# Power.net
KiCad netlist of a schematic drawn in Altium Designer
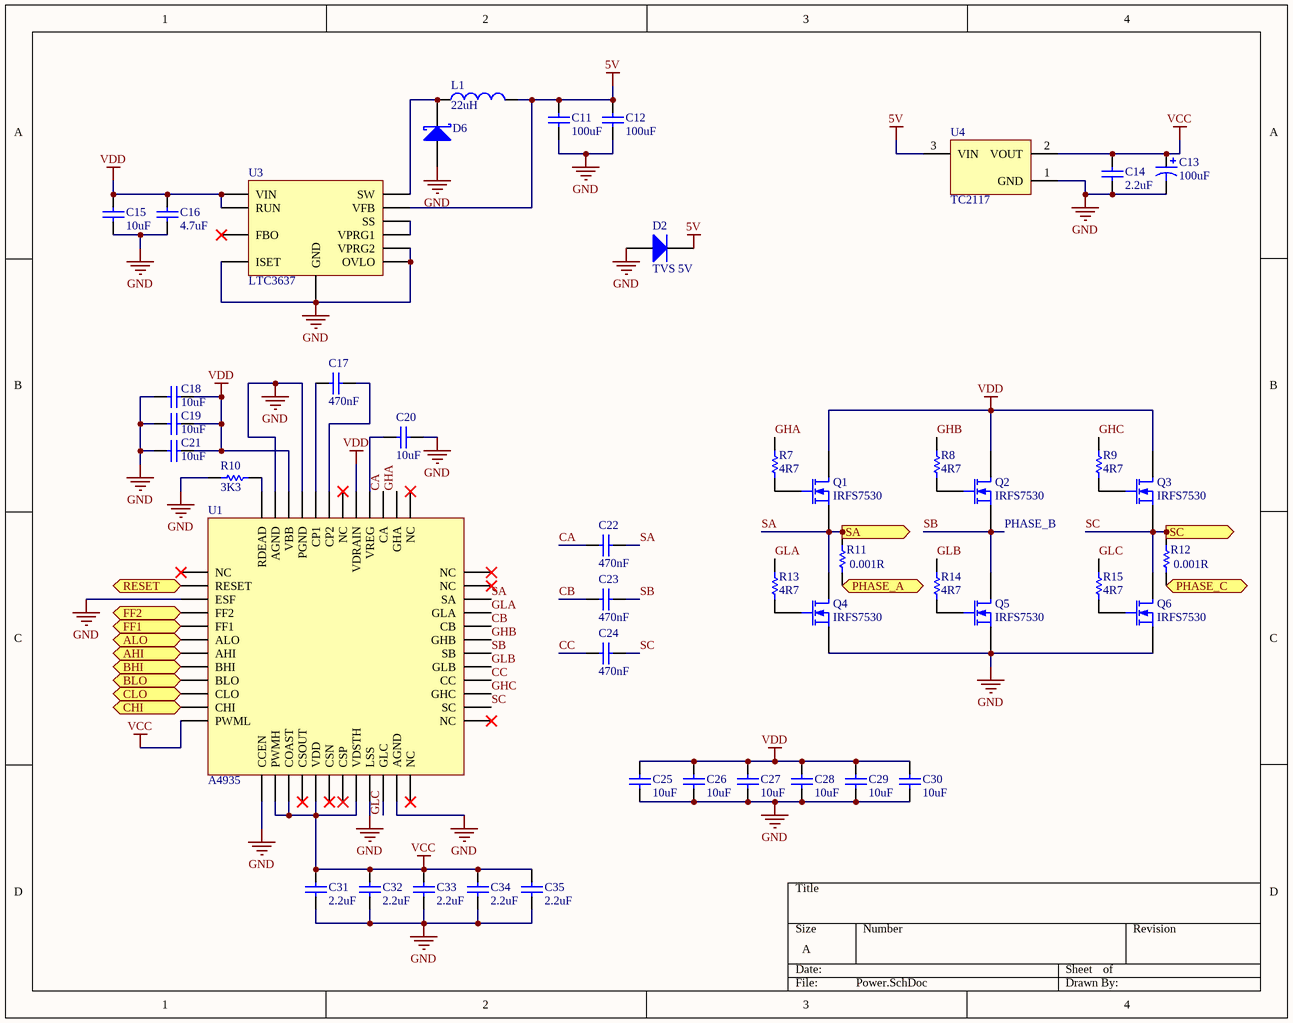
[diagram p0: Power.SchDoc]

(export (version "E")
  (design (tool "Eeschema 10.0.6"))
  (components
    (comp (ref "C11")
      (value "100uF")
      (footprint "CAPC1210(3225)280_N")
      (description "CAP 100uF 10V Â±10% 1210 (3225 Metric) Thickness 2.8mm SMD")
      (fields (field (name "TOLERANCE") "Â±10%"))
      (libsource (lib "Altium Content Vault") (part "CMP-1038-02301-1"))
    )
    (comp (ref "C12")
      (value "100uF")
      (footprint "CAPC1210(3225)280_N")
      (description "CAP 100uF 10V Â±10% 1210 (3225 Metric) Thickness 2.8mm SMD")
      (fields (field (name "TOLERANCE") "Â±10%"))
      (libsource (lib "Altium Content Vault") (part "CMP-1038-02301-1"))
    )
    (comp (ref "C13")
      (value "100uF")
      (footprint "AVX-CAPC7343_V")
      (libsource (lib "Components") (part "AVX-CAP-P-2"))
    )
    (comp (ref "C14")
      (value "2.2uF")
      (footprint "CAPC0603(1608)55_N")
      (description "CAP 2.2uF 16V Â±10% 0603 (1608 Metric) Thickness 0.55mm SMD")
      (fields (field (name "TOLERANCE") "Â±10%"))
      (libsource (lib "Altium Content Vault") (part "CMP-1035-02762-1"))
    )
    (comp (ref "C15")
      (value "10uF")
      (footprint "CAPC1206(3216)190_M")
      (description "CAP 10uF 50V Â±10% 1206 (3216 Metric) Thickness 1.9mm SMD")
      (fields (field (name "TOLERANCE") "Â±10%"))
      (libsource (lib "Altium Content Vault") (part "CAP"))
    )
    (comp (ref "C16")
      (value "4.7uF")
      (footprint "CAPC0805(2012)145_N")
      (description "CAP 4.7uF 50V Â±10% 0805 (2012 Metric) Thickness 1.45mm SMD")
      (fields (field (name "TOLERANCE") "Â±10%"))
      (libsource (lib "Altium Content Vault") (part "CAP"))
    )
    (comp (ref "C17")
      (value "470nF")
      (footprint "CAPC0603(1608)100_N")
      (description "CAP 470nF 25V Â±20% 0603 (1608 Metric) Thickness 1mm SMD")
      (fields (field (name "TOLERANCE") "Â±20%"))
      (libsource (lib "Altium Content Vault") (part "CAP"))
    )
    (comp (ref "C18")
      (value "10uF")
      (footprint "CAPC1206(3216)190_M")
      (description "CAP 10uF 50V Â±10% 1206 (3216 Metric) Thickness 1.9mm SMD")
      (fields (field (name "TOLERANCE") "Â±10%"))
      (libsource (lib "Altium Content Vault") (part "CAP"))
    )
    (comp (ref "C19")
      (value "10uF")
      (footprint "CAPC1206(3216)190_M")
      (description "CAP 10uF 50V Â±10% 1206 (3216 Metric) Thickness 1.9mm SMD")
      (fields (field (name "TOLERANCE") "Â±10%"))
      (libsource (lib "Altium Content Vault") (part "CAP"))
    )
    (comp (ref "C20")
      (value "10uF")
      (footprint "CAPC0805(2012)145_N")
      (description "CAP 10uF 25V Â±10% 0805 (2012 Metric) Thickness 1.45mm SMD")
      (fields (field (name "TOLERANCE") "Â±10%"))
      (libsource (lib "Altium Content Vault") (part "CAP"))
    )
    (comp (ref "C21")
      (value "10uF")
      (footprint "CAPC1206(3216)190_M")
      (description "CAP 10uF 50V Â±10% 1206 (3216 Metric) Thickness 1.9mm SMD")
      (fields (field (name "TOLERANCE") "Â±10%"))
      (libsource (lib "Altium Content Vault") (part "CAP"))
    )
    (comp (ref "C22")
      (value "470nF")
      (footprint "CAPC0603(1608)100_L")
      (description "CAP 470nF 25V Â±10% 0603 (1608 Metric) Thickness 1mm SMD")
      (fields (field (name "TOLERANCE") "Â±10%"))
      (libsource (lib "Altium Content Vault") (part "CAP"))
    )
    (comp (ref "C23")
      (value "470nF")
      (footprint "CAPC0603(1608)100_L")
      (description "CAP 470nF 25V Â±10% 0603 (1608 Metric) Thickness 1mm SMD")
      (fields (field (name "TOLERANCE") "Â±10%"))
      (libsource (lib "Altium Content Vault") (part "CAP"))
    )
    (comp (ref "C24")
      (value "470nF")
      (footprint "CAPC0603(1608)100_L")
      (description "CAP 470nF 25V Â±10% 0603 (1608 Metric) Thickness 1mm SMD")
      (fields (field (name "TOLERANCE") "Â±10%"))
      (libsource (lib "Altium Content Vault") (part "CAP"))
    )
    (comp (ref "C25")
      (value "10uF")
      (footprint "CAPC1206(3216)190_M")
      (description "CAP 10uF 50V Â±10% 1206 (3216 Metric) Thickness 1.9mm SMD")
      (fields (field (name "TOLERANCE") "Â±10%"))
      (libsource (lib "Altium Content Vault") (part "CMP-1037-04982-1"))
    )
    (comp (ref "C26")
      (value "10uF")
      (footprint "CAPC1206(3216)190_M")
      (description "CAP 10uF 50V Â±10% 1206 (3216 Metric) Thickness 1.9mm SMD")
      (fields (field (name "TOLERANCE") "Â±10%"))
      (libsource (lib "Altium Content Vault") (part "CAP"))
    )
    (comp (ref "C27")
      (value "10uF")
      (footprint "CAPC1206(3216)190_M")
      (description "CAP 10uF 50V Â±10% 1206 (3216 Metric) Thickness 1.9mm SMD")
      (fields (field (name "TOLERANCE") "Â±10%"))
      (libsource (lib "Altium Content Vault") (part "CAP"))
    )
    (comp (ref "C28")
      (value "10uF")
      (footprint "CAPC1206(3216)190_M")
      (description "CAP 10uF 50V Â±10% 1206 (3216 Metric) Thickness 1.9mm SMD")
      (fields (field (name "TOLERANCE") "Â±10%"))
      (libsource (lib "Altium Content Vault") (part "CMP-1037-04982-1"))
    )
    (comp (ref "C29")
      (value "10uF")
      (footprint "CAPC1206(3216)190_M")
      (description "CAP 10uF 50V Â±10% 1206 (3216 Metric) Thickness 1.9mm SMD")
      (fields (field (name "TOLERANCE") "Â±10%"))
      (libsource (lib "Altium Content Vault") (part "CAP"))
    )
    (comp (ref "C30")
      (value "10uF")
      (footprint "CAPC1206(3216)190_M")
      (description "CAP 10uF 50V Â±10% 1206 (3216 Metric) Thickness 1.9mm SMD")
      (fields (field (name "TOLERANCE") "Â±10%"))
      (libsource (lib "Altium Content Vault") (part "CAP"))
    )
    (comp (ref "C31")
      (value "2.2uF")
      (footprint "CAPC0603(1608)55_N")
      (description "CAP 2.2uF 16V Â±10% 0603 (1608 Metric) Thickness 0.55mm SMD")
      (fields (field (name "TOLERANCE") "Â±10%"))
      (libsource (lib "Altium Content Vault") (part "CMP-1035-02762-1"))
    )
    (comp (ref "C32")
      (value "2.2uF")
      (footprint "CAPC0603(1608)55_N")
      (description "CAP 2.2uF 16V Â±10% 0603 (1608 Metric) Thickness 0.55mm SMD")
      (fields (field (name "TOLERANCE") "Â±10%"))
      (libsource (lib "Altium Content Vault") (part "CMP-1035-02762-1"))
    )
    (comp (ref "C33")
      (value "2.2uF")
      (footprint "CAPC0603(1608)55_N")
      (description "CAP 2.2uF 16V Â±10% 0603 (1608 Metric) Thickness 0.55mm SMD")
      (fields (field (name "TOLERANCE") "Â±10%"))
      (libsource (lib "Altium Content Vault") (part "CMP-1035-02762-1"))
    )
    (comp (ref "C34")
      (value "2.2uF")
      (footprint "CAPC0603(1608)55_N")
      (description "CAP 2.2uF 16V Â±10% 0603 (1608 Metric) Thickness 0.55mm SMD")
      (fields (field (name "TOLERANCE") "Â±10%"))
      (libsource (lib "Altium Content Vault") (part "CMP-1035-02762-1"))
    )
    (comp (ref "C35")
      (value "2.2uF")
      (footprint "CAPC0603(1608)55_N")
      (description "CAP 2.2uF 16V Â±10% 0603 (1608 Metric) Thickness 0.55mm SMD")
      (fields (field (name "TOLERANCE") "Â±10%"))
      (libsource (lib "Altium Content Vault") (part "CMP-1035-02762-1"))
    )
    (comp (ref "D2")
      (value "TVS 5V")
      (footprint "VISH-DO-214AC-2_N")
      (fields
        (field (name "PARTNUMBER") "SMAJ5.0A-E3/61")
        (field (name "MANUFACTURER") "Vishay Semiconductor")
      )
      (libsource (lib "Altium Content Vault") (part "CMP-0548-00235-1"))
    )
    (comp (ref "D6")
      (value "~")
      (footprint "SMB")
      (description "Schottky Diode")
      (fields (field (name "PUBLISHER") "Altium Limited"))
      (libsource (lib "Miscellaneous Devices") (part "D Schottky"))
    )
    (comp (ref "L1")
      (value "22uH")
      (footprint "SDR0805-180ML")
      (description "Inductor")
      (fields (field (name "Comment") "SDR0805-180ML") (field (name "PUBLISHER") "Altium Limited"))
      (libsource (lib "Components") (part "SDR0805-180ML"))
    )
    (comp (ref "Q1")
      (value "IRFS7530")
      (footprint "DPAK127P1525X483-7N")
      (description "N-Channel MOSFET")
      (fields (field (name "PUBLISHER") "Altium Limited"))
      (libsource (lib "Components") (part "IRFS7530"))
    )
    (comp (ref "Q2")
      (value "IRFS7530")
      (footprint "DPAK127P1525X483-7N")
      (description "N-Channel MOSFET")
      (fields (field (name "PUBLISHER") "Altium Limited"))
      (libsource (lib "Components") (part "IRFS7530"))
    )
    (comp (ref "Q3")
      (value "IRFS7530")
      (footprint "DPAK127P1525X483-7N")
      (description "N-Channel MOSFET")
      (fields (field (name "PUBLISHER") "Altium Limited"))
      (libsource (lib "Components") (part "IRFS7530"))
    )
    (comp (ref "Q4")
      (value "IRFS7530")
      (footprint "DPAK127P1525X483-7N")
      (description "N-Channel MOSFET")
      (fields (field (name "PUBLISHER") "Altium Limited"))
      (libsource (lib "Components") (part "IRFS7530"))
    )
    (comp (ref "Q5")
      (value "IRFS7530")
      (footprint "DPAK127P1525X483-7N")
      (description "N-Channel MOSFET")
      (fields (field (name "PUBLISHER") "Altium Limited"))
      (libsource (lib "Components") (part "IRFS7530"))
    )
    (comp (ref "Q6")
      (value "IRFS7530")
      (footprint "DPAK127P1525X483-7N")
      (description "N-Channel MOSFET")
      (fields (field (name "PUBLISHER") "Altium Limited"))
      (libsource (lib "Components") (part "IRFS7530"))
    )
    (comp (ref "R7")
      (value "4R7")
      (footprint "RESC0603(1608)_N")
      (description "4R7 0.1W 5% 0603 (1608 Metric)  SMD")
      (fields (field (name "POWER") "0.1 W") (field (name "TOLERANCE") "5 %"))
      (libsource (lib "Altium Content Vault") (part "CMP-1012-00018-1"))
    )
    (comp (ref "R8")
      (value "4R7")
      (footprint "RESC0603(1608)_N")
      (description "4R7 0.1W 5% 0603 (1608 Metric)  SMD")
      (fields (field (name "POWER") "0.1 W") (field (name "TOLERANCE") "5 %"))
      (libsource (lib "Altium Content Vault") (part "CMP-1012-00018-1"))
    )
    (comp (ref "R9")
      (value "4R7")
      (footprint "RESC0603(1608)_N")
      (description "4R7 0.1W 5% 0603 (1608 Metric)  SMD")
      (fields (field (name "POWER") "0.1 W") (field (name "TOLERANCE") "5 %"))
      (libsource (lib "Altium Content Vault") (part "CMP-1012-00018-1"))
    )
    (comp (ref "R10")
      (value "3K3")
      (footprint "RESC0603(1608)_N")
      (description "3K3 0.1W 5% 0603 (1608 Metric)  SMD")
      (fields (field (name "TOLERANCE") "5 %") (field (name "POWER") "0.1 W"))
      (libsource (lib "Altium Content Vault") (part "CMP-1012-00086-1"))
    )
    (comp (ref "R11")
      (value "0.001R")
      (footprint "Shunt")
      (fields (field (name "PUBLISHER") "Altium Limited"))
      (libsource (lib "Components") (part "Shunt"))
    )
    (comp (ref "R12")
      (value "0.001R")
      (footprint "Shunt")
      (description "Resistor")
      (fields (field (name "PUBLISHER") "Altium Limited"))
      (libsource (lib "Components") (part "Shunt"))
    )
    (comp (ref "R13")
      (value "4R7")
      (footprint "RESC0603(1608)_N")
      (description "4R7 0.1W 5% 0603 (1608 Metric)  SMD")
      (fields (field (name "POWER") "0.1 W") (field (name "TOLERANCE") "5 %"))
      (libsource (lib "Altium Content Vault") (part "CMP-1012-00018-1"))
    )
    (comp (ref "R14")
      (value "4R7")
      (footprint "RESC0603(1608)_N")
      (description "4R7 0.1W 5% 0603 (1608 Metric)  SMD")
      (fields (field (name "POWER") "0.1 W") (field (name "TOLERANCE") "5 %"))
      (libsource (lib "Altium Content Vault") (part "CMP-1012-00018-1"))
    )
    (comp (ref "R15")
      (value "4R7")
      (footprint "RESC0603(1608)_N")
      (description "4R7 0.1W 5% 0603 (1608 Metric)  SMD")
      (fields (field (name "POWER") "0.1 W") (field (name "TOLERANCE") "5 %"))
      (libsource (lib "Altium Content Vault") (part "CMP-1012-00018-1"))
    )
    (comp (ref "U1") (value "A4935") (footprint "LQFP-48") (libsource (lib "Components") (part "A4935")))
    (comp (ref "U3")
      (value "LTC3637")
      (footprint "SON50P300X85_HS-17N")
      (libsource (lib "Components") (part "LTC3637"))
    )
    (comp (ref "U4")
      (value "TC2117")
      (footprint "SOT-223-DB3_M")
      (libsource (lib "Components") (part "PM-LINEREG-TC2117-IL4"))
    )
  )
  (nets
    (net (code "1") (name "/AHI") (class "Default")
      (node (ref "U1") (pin "7") (pinfunction "AHI_7") (pintype "passive"))
    )
    (net (code "2") (name "/ALO") (class "Default")
      (node (ref "U1") (pin "6") (pinfunction "ALO_6") (pintype "passive"))
    )
    (net (code "3") (name "/BHI") (class "Default")
      (node (ref "U1") (pin "8") (pinfunction "BHI_8") (pintype "passive"))
    )
    (net (code "4") (name "/BLO") (class "Default")
      (node (ref "U1") (pin "9") (pinfunction "BLO_9") (pintype "passive"))
    )
    (net (code "5") (name "/CA") (class "Default")
      (node (ref "C22") (pin "1") (pinfunction "1_1") (pintype "passive"))
      (node (ref "U1") (pin "39") (pinfunction "CA_39") (pintype "passive"))
    )
    (net (code "6") (name "/CB") (class "Default")
      (node (ref "C23") (pin "1") (pinfunction "1_1") (pintype "passive"))
      (node (ref "U1") (pin "32") (pinfunction "CB_32") (pintype "passive"))
    )
    (net (code "7") (name "/CC") (class "Default")
      (node (ref "C24") (pin "1") (pinfunction "1_1") (pintype "passive"))
      (node (ref "U1") (pin "28") (pinfunction "CC_28") (pintype "passive"))
    )
    (net (code "8") (name "/CHI") (class "Default")
      (node (ref "U1") (pin "11") (pinfunction "CHI_11") (pintype "passive"))
    )
    (net (code "9") (name "/CLO") (class "Default")
      (node (ref "U1") (pin "10") (pinfunction "CLO_10") (pintype "passive"))
    )
    (net (code "10") (name "/FF1") (class "Default")
      (node (ref "U1") (pin "5") (pinfunction "FF1_5") (pintype "passive"))
    )
    (net (code "11") (name "/FF2") (class "Default")
      (node (ref "U1") (pin "4") (pinfunction "FF2_4") (pintype "passive"))
    )
    (net (code "12") (name "/GHA") (class "Default")
      (node (ref "R7") (pin "2") (pinfunction "2_2") (pintype "passive"))
      (node (ref "U1") (pin "38") (pinfunction "GHA_38") (pintype "passive"))
    )
    (net (code "13") (name "/GHB") (class "Default")
      (node (ref "R8") (pin "2") (pinfunction "2_2") (pintype "passive"))
      (node (ref "U1") (pin "31") (pinfunction "GHB_31") (pintype "passive"))
    )
    (net (code "14") (name "/GHC") (class "Default")
      (node (ref "R9") (pin "2") (pinfunction "2_2") (pintype "passive"))
      (node (ref "U1") (pin "27") (pinfunction "GHC_27") (pintype "passive"))
    )
    (net (code "15") (name "/GLA") (class "Default")
      (node (ref "R13") (pin "2") (pinfunction "2_2") (pintype "passive"))
      (node (ref "U1") (pin "33") (pinfunction "GLA_33") (pintype "passive"))
    )
    (net (code "16") (name "/GLB") (class "Default")
      (node (ref "R14") (pin "2") (pinfunction "2_2") (pintype "passive"))
      (node (ref "U1") (pin "29") (pinfunction "GLB_29") (pintype "passive"))
    )
    (net (code "17") (name "/GLC") (class "Default")
      (node (ref "R15") (pin "2") (pinfunction "2_2") (pintype "passive"))
      (node (ref "U1") (pin "22") (pinfunction "GLC_22") (pintype "passive"))
    )
    (net (code "18") (name "/PHASE_A") (class "Default")
      (node (ref "R11") (pin "1") (pinfunction "1_1") (pintype "passive"))
    )
    (net (code "19") (name "/PHASE_C") (class "Default")
      (node (ref "R12") (pin "1") (pinfunction "1_1") (pintype "passive"))
    )
    (net (code "20") (name "/RESET") (class "Default")
      (node (ref "U1") (pin "2") (pinfunction "RESET_2") (pintype "passive"))
    )
    (net (code "21") (name "/SA") (class "Default")
      (node (ref "C22") (pin "2") (pinfunction "2_2") (pintype "passive"))
      (node (ref "Q1") (pin "3") (pinfunction "S_3") (pintype "passive"))
      (node (ref "Q4") (pin "1") (pinfunction "D_1") (pintype "passive"))
      (node (ref "R11") (pin "2") (pinfunction "2_2") (pintype "passive"))
      (node (ref "U1") (pin "34") (pinfunction "SA_34") (pintype "passive"))
    )
    (net (code "22") (name "/SB") (class "Default")
      (node (ref "C23") (pin "2") (pinfunction "2_2") (pintype "passive"))
      (node (ref "Q2") (pin "3") (pinfunction "S_3") (pintype "passive"))
      (node (ref "Q5") (pin "1") (pinfunction "D_1") (pintype "passive"))
      (node (ref "U1") (pin "30") (pinfunction "SB_30") (pintype "passive"))
    )
    (net (code "23") (name "/SC") (class "Default")
      (node (ref "C24") (pin "2") (pinfunction "2_2") (pintype "passive"))
      (node (ref "Q3") (pin "3") (pinfunction "S_3") (pintype "passive"))
      (node (ref "Q6") (pin "1") (pinfunction "D_1") (pintype "passive"))
      (node (ref "R12") (pin "2") (pinfunction "2_2") (pintype "passive"))
      (node (ref "U1") (pin "26") (pinfunction "SC_26") (pintype "passive"))
    )
    (net (code "24") (name "5V") (class "Default")
      (node (ref "C11") (pin "2") (pinfunction "2_2") (pintype "passive"))
      (node (ref "C12") (pin "2") (pinfunction "2_2") (pintype "passive"))
      (node (ref "D2") (pin "1") (pinfunction "K_1") (pintype "passive"))
      (node (ref "L1") (pin "2") (pinfunction "2_2") (pintype "passive"))
      (node (ref "U3") (pin "9") (pinfunction "VFB_9") (pintype "passive"))
      (node (ref "U4") (pin "3") (pinfunction "VIN_3") (pintype "power_in"))
    )
    (net (code "25") (name "GND") (class "Default")
      (node (ref "C11") (pin "1") (pinfunction "1_1") (pintype "passive"))
      (node (ref "C12") (pin "1") (pinfunction "1_1") (pintype "passive"))
      (node (ref "C13") (pin "2") (pinfunction "2_2") (pintype "passive"))
      (node (ref "C14") (pin "2") (pinfunction "2_2") (pintype "passive"))
      (node (ref "C15") (pin "1") (pinfunction "1_1") (pintype "passive"))
      (node (ref "C16") (pin "2") (pinfunction "2_2") (pintype "passive"))
      (node (ref "C18") (pin "1") (pinfunction "1_1") (pintype "passive"))
      (node (ref "C19") (pin "1") (pinfunction "1_1") (pintype "passive"))
      (node (ref "C20") (pin "2") (pinfunction "2_2") (pintype "passive"))
      (node (ref "C21") (pin "1") (pinfunction "1_1") (pintype "passive"))
      (node (ref "C25") (pin "1") (pinfunction "1_1") (pintype "passive"))
      (node (ref "C26") (pin "1") (pinfunction "1_1") (pintype "passive"))
      (node (ref "C27") (pin "1") (pinfunction "1_1") (pintype "passive"))
      (node (ref "C28") (pin "1") (pinfunction "1_1") (pintype "passive"))
      (node (ref "C29") (pin "1") (pinfunction "1_1") (pintype "passive"))
      (node (ref "C30") (pin "1") (pinfunction "1_1") (pintype "passive"))
      (node (ref "C31") (pin "1") (pinfunction "1_1") (pintype "passive"))
      (node (ref "C32") (pin "1") (pinfunction "1_1") (pintype "passive"))
      (node (ref "C33") (pin "1") (pinfunction "1_1") (pintype "passive"))
      (node (ref "C34") (pin "1") (pinfunction "1_1") (pintype "passive"))
      (node (ref "C35") (pin "1") (pinfunction "1_1") (pintype "passive"))
      (node (ref "D2") (pin "2") (pinfunction "A_2") (pintype "passive"))
      (node (ref "D6") (pin "1") (pinfunction "A_1") (pintype "passive"))
      (node (ref "Q4") (pin "3") (pinfunction "S_3") (pintype "passive"))
      (node (ref "Q5") (pin "3") (pinfunction "S_3") (pintype "passive"))
      (node (ref "Q6") (pin "3") (pinfunction "S_3") (pintype "passive"))
      (node (ref "R10") (pin "1") (pinfunction "1_1") (pintype "passive"))
      (node (ref "U1") (pin "13") (pinfunction "CCEN_13") (pintype "passive"))
      (node (ref "U1") (pin "21") (pinfunction "LSS_21") (pintype "passive"))
      (node (ref "U1") (pin "23") (pinfunction "AGND_23") (pintype "passive"))
      (node (ref "U1") (pin "3") (pinfunction "ESF_3") (pintype "passive"))
      (node (ref "U1") (pin "45") (pinfunction "PGND_45") (pintype "passive"))
      (node (ref "U1") (pin "47") (pinfunction "AGND_47") (pintype "passive"))
      (node (ref "U3") (pin "11") (pinfunction "ISET_11") (pintype "passive"))
      (node (ref "U3") (pin "12") (pinfunction "OVLO_12") (pintype "passive"))
      (node (ref "U3") (pin "17") (pinfunction "GND_17") (pintype "passive"))
      (node (ref "U3") (pin "6") (pinfunction "VPRG2_6") (pintype "passive"))
      (node (ref "U4") (pin "1") (pinfunction "GND_1") (pintype "power_in"))
    )
    (net (code "26") (name "Net-(D6-K)") (class "Default")
      (node (ref "D6") (pin "2") (pinfunction "K_2") (pintype "passive"))
      (node (ref "L1") (pin "1") (pinfunction "1_1") (pintype "passive"))
      (node (ref "U3") (pin "1") (pinfunction "SW_1") (pintype "passive"))
    )
    (net (code "27") (name "Net-(Q1-G)") (class "Default")
      (node (ref "Q1") (pin "2") (pinfunction "G_2") (pintype "passive"))
      (node (ref "R7") (pin "1") (pinfunction "1_1") (pintype "passive"))
    )
    (net (code "28") (name "Net-(Q2-G)") (class "Default")
      (node (ref "Q2") (pin "2") (pinfunction "G_2") (pintype "passive"))
      (node (ref "R8") (pin "1") (pinfunction "1_1") (pintype "passive"))
    )
    (net (code "29") (name "Net-(Q3-G)") (class "Default")
      (node (ref "Q3") (pin "2") (pinfunction "G_2") (pintype "passive"))
      (node (ref "R9") (pin "1") (pinfunction "1_1") (pintype "passive"))
    )
    (net (code "30") (name "Net-(Q4-G)") (class "Default")
      (node (ref "Q4") (pin "2") (pinfunction "G_2") (pintype "passive"))
      (node (ref "R13") (pin "1") (pinfunction "1_1") (pintype "passive"))
    )
    (net (code "31") (name "Net-(Q5-G)") (class "Default")
      (node (ref "Q5") (pin "2") (pinfunction "G_2") (pintype "passive"))
      (node (ref "R14") (pin "1") (pinfunction "1_1") (pintype "passive"))
    )
    (net (code "32") (name "Net-(Q6-G)") (class "Default")
      (node (ref "Q6") (pin "2") (pinfunction "G_2") (pintype "passive"))
      (node (ref "R15") (pin "1") (pinfunction "1_1") (pintype "passive"))
    )
    (net (code "33") (name "Net-(U1-CP1)") (class "Default")
      (node (ref "C17") (pin "1") (pinfunction "1_1") (pintype "passive"))
      (node (ref "U1") (pin "44") (pinfunction "CP1_44") (pintype "passive"))
    )
    (net (code "34") (name "Net-(U1-CP2)") (class "Default")
      (node (ref "C17") (pin "2") (pinfunction "2_2") (pintype "passive"))
      (node (ref "U1") (pin "43") (pinfunction "CP2_43") (pintype "passive"))
    )
    (net (code "35") (name "Net-(U1-RDEAD)") (class "Default")
      (node (ref "R10") (pin "2") (pinfunction "2_2") (pintype "passive"))
      (node (ref "U1") (pin "48") (pinfunction "RDEAD_48") (pintype "passive"))
    )
    (net (code "36") (name "Net-(U1-VREG)") (class "Default")
      (node (ref "C20") (pin "1") (pinfunction "1_1") (pintype "passive"))
      (node (ref "U1") (pin "40") (pinfunction "VREG_40") (pintype "passive"))
    )
    (net (code "37") (name "Net-(U3-SS)") (class "Default")
      (node (ref "U3") (pin "10") (pinfunction "SS_10") (pintype "passive"))
      (node (ref "U3") (pin "7") (pinfunction "VPRG1_7") (pintype "passive"))
    )
    (net (code "38") (name "VCC") (class "Default")
      (node (ref "C13") (pin "1") (pinfunction "1_1") (pintype "passive"))
      (node (ref "C14") (pin "1") (pinfunction "1_1") (pintype "passive"))
      (node (ref "C31") (pin "2") (pinfunction "2_2") (pintype "passive"))
      (node (ref "C32") (pin "2") (pinfunction "2_2") (pintype "passive"))
      (node (ref "C33") (pin "2") (pinfunction "2_2") (pintype "passive"))
      (node (ref "C34") (pin "2") (pinfunction "2_2") (pintype "passive"))
      (node (ref "C35") (pin "2") (pinfunction "2_2") (pintype "passive"))
      (node (ref "U1") (pin "12") (pinfunction "PWML_12") (pintype "passive"))
      (node (ref "U1") (pin "14") (pinfunction "PWMH_14") (pintype "passive"))
      (node (ref "U1") (pin "15") (pinfunction "COAST_15") (pintype "passive"))
      (node (ref "U1") (pin "17") (pinfunction "VDD_17") (pintype "passive"))
      (node (ref "U1") (pin "20") (pinfunction "VDSTH_20") (pintype "passive"))
      (node (ref "U4") (pin "2") (pinfunction "VOUT_2") (pintype "power_in"))
    )
    (net (code "39") (name "VDD") (class "Default")
      (node (ref "C15") (pin "2") (pinfunction "2_2") (pintype "passive"))
      (node (ref "C16") (pin "1") (pinfunction "1_1") (pintype "passive"))
      (node (ref "C18") (pin "2") (pinfunction "2_2") (pintype "passive"))
      (node (ref "C19") (pin "2") (pinfunction "2_2") (pintype "passive"))
      (node (ref "C21") (pin "2") (pinfunction "2_2") (pintype "passive"))
      (node (ref "C25") (pin "2") (pinfunction "2_2") (pintype "passive"))
      (node (ref "C26") (pin "2") (pinfunction "2_2") (pintype "passive"))
      (node (ref "C27") (pin "2") (pinfunction "2_2") (pintype "passive"))
      (node (ref "C28") (pin "2") (pinfunction "2_2") (pintype "passive"))
      (node (ref "C29") (pin "2") (pinfunction "2_2") (pintype "passive"))
      (node (ref "C30") (pin "2") (pinfunction "2_2") (pintype "passive"))
      (node (ref "Q1") (pin "1") (pinfunction "D_1") (pintype "passive"))
      (node (ref "Q2") (pin "1") (pinfunction "D_1") (pintype "passive"))
      (node (ref "Q3") (pin "1") (pinfunction "D_1") (pintype "passive"))
      (node (ref "U1") (pin "41") (pinfunction "VDRAIN_41") (pintype "passive"))
      (node (ref "U1") (pin "46") (pinfunction "VBB_46") (pintype "passive"))
      (node (ref "U3") (pin "14") (pinfunction "RUN_14") (pintype "passive"))
      (node (ref "U3") (pin "3") (pinfunction "VIN_3") (pintype "passive"))
    )
    (net (code "40") (name "unconnected-(U1-CSN-Pad18)") (class "Default")
      (node (ref "U1") (pin "18") (pinfunction "CSN_18") (pintype "passive+no_connect"))
    )
    (net (code "41") (name "unconnected-(U1-CSOUT-Pad16)") (class "Default")
      (node (ref "U1") (pin "16") (pinfunction "CSOUT_16") (pintype "passive+no_connect"))
    )
    (net (code "42") (name "unconnected-(U1-CSP-Pad19)") (class "Default")
      (node (ref "U1") (pin "19") (pinfunction "CSP_19") (pintype "passive+no_connect"))
    )
    (net (code "43") (name "unconnected-(U1-NC-Pad1)") (class "Default")
      (node (ref "U1") (pin "1") (pinfunction "NC_1") (pintype "passive+no_connect"))
    )
    (net (code "44") (name "unconnected-(U1-NC-Pad24)") (class "Default")
      (node (ref "U1") (pin "24") (pinfunction "NC_24") (pintype "passive+no_connect"))
    )
    (net (code "45") (name "unconnected-(U1-NC-Pad25)") (class "Default")
      (node (ref "U1") (pin "25") (pinfunction "NC_25") (pintype "passive+no_connect"))
    )
    (net (code "46") (name "unconnected-(U1-NC-Pad35)") (class "Default")
      (node (ref "U1") (pin "35") (pinfunction "NC_35") (pintype "passive+no_connect"))
    )
    (net (code "47") (name "unconnected-(U1-NC-Pad36)") (class "Default")
      (node (ref "U1") (pin "36") (pinfunction "NC_36") (pintype "passive+no_connect"))
    )
    (net (code "48") (name "unconnected-(U1-NC-Pad37)") (class "Default")
      (node (ref "U1") (pin "37") (pinfunction "NC_37") (pintype "passive+no_connect"))
    )
    (net (code "49") (name "unconnected-(U1-NC-Pad42)") (class "Default")
      (node (ref "U1") (pin "42") (pinfunction "NC_42") (pintype "passive+no_connect"))
    )
    (net (code "50") (name "unconnected-(U3-FBO-Pad5)") (class "Default")
      (node (ref "U3") (pin "5") (pinfunction "FBO_5") (pintype "passive+no_connect"))
    )
  )
)
